# USB_V4.net
KiCad netlist of a schematic drawn in Altium Designer
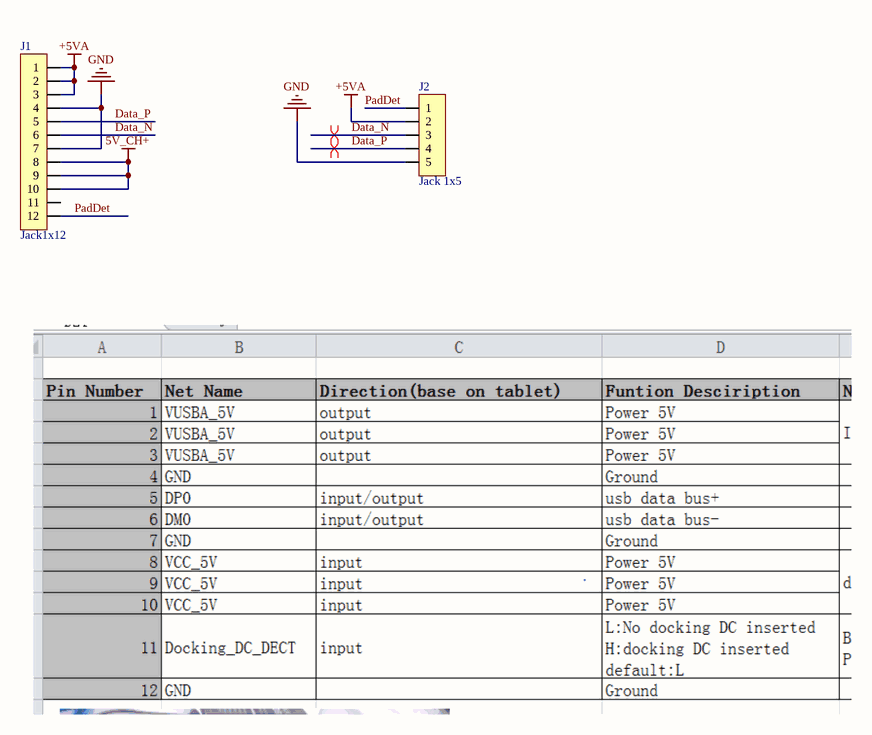
[diagram p0: 海关全向控制器USB转接板V4.SchDoc]

(export (version "E")
  (design (tool "Eeschema 10.0.6"))
  (components
    (comp (ref "J1")
      (value "Jack1x12")
      (footprint "PPM.12-711-0102")
      (description "插座")
      (libsource (lib "Connector") (part "Jack1x12"))
    )
    (comp (ref "J2")
      (value "Jack 1x5")
      (footprint "35363-0560")
      (description "插座")
      (libsource (lib "Connector") (part "Jack 1x5"))
    )
  )
  (nets
    (net (code "1") (name "+5VA") (class "Default")
      (node (ref "J1") (pin "1") (pinfunction "1_1") (pintype "passive"))
      (node (ref "J1") (pin "2") (pinfunction "2_2") (pintype "passive"))
      (node (ref "J1") (pin "3") (pinfunction "3_3") (pintype "passive"))
      (node (ref "J2") (pin "2") (pinfunction "2_2") (pintype "passive"))
    )
    (net (code "2") (name "/Data_N") (class "Default")
      (node (ref "J1") (pin "6") (pinfunction "6_6") (pintype "passive"))
      (node (ref "J2") (pin "3") (pinfunction "3_3") (pintype "passive"))
    )
    (net (code "3") (name "/Data_P") (class "Default")
      (node (ref "J1") (pin "5") (pinfunction "5_5") (pintype "passive"))
      (node (ref "J2") (pin "4") (pinfunction "4_4") (pintype "passive"))
    )
    (net (code "4") (name "/PadDet") (class "Default")
      (node (ref "J1") (pin "12") (pinfunction "12_12") (pintype "passive"))
      (node (ref "J2") (pin "1") (pinfunction "1_1") (pintype "passive"))
    )
    (net (code "5") (name "5V_CH+") (class "Default")
      (node (ref "J1") (pin "10") (pinfunction "10_10") (pintype "passive"))
      (node (ref "J1") (pin "8") (pinfunction "8_8") (pintype "passive"))
      (node (ref "J1") (pin "9") (pinfunction "9_9") (pintype "passive"))
    )
    (net (code "6") (name "GND") (class "Default")
      (node (ref "J1") (pin "4") (pinfunction "4_4") (pintype "passive"))
      (node (ref "J1") (pin "7") (pinfunction "7_7") (pintype "passive"))
      (node (ref "J2") (pin "5") (pinfunction "5_5") (pintype "passive"))
    )
    (net (code "7") (name "unconnected-(J1-Pad11)") (class "Default")
      (node (ref "J1") (pin "11") (pinfunction "11_11") (pintype "passive"))
    )
  )
)
